# ProDoc_ChisFlash-Celebi.net
KiCad netlist of a schematic drawn in EasyEDA Pro
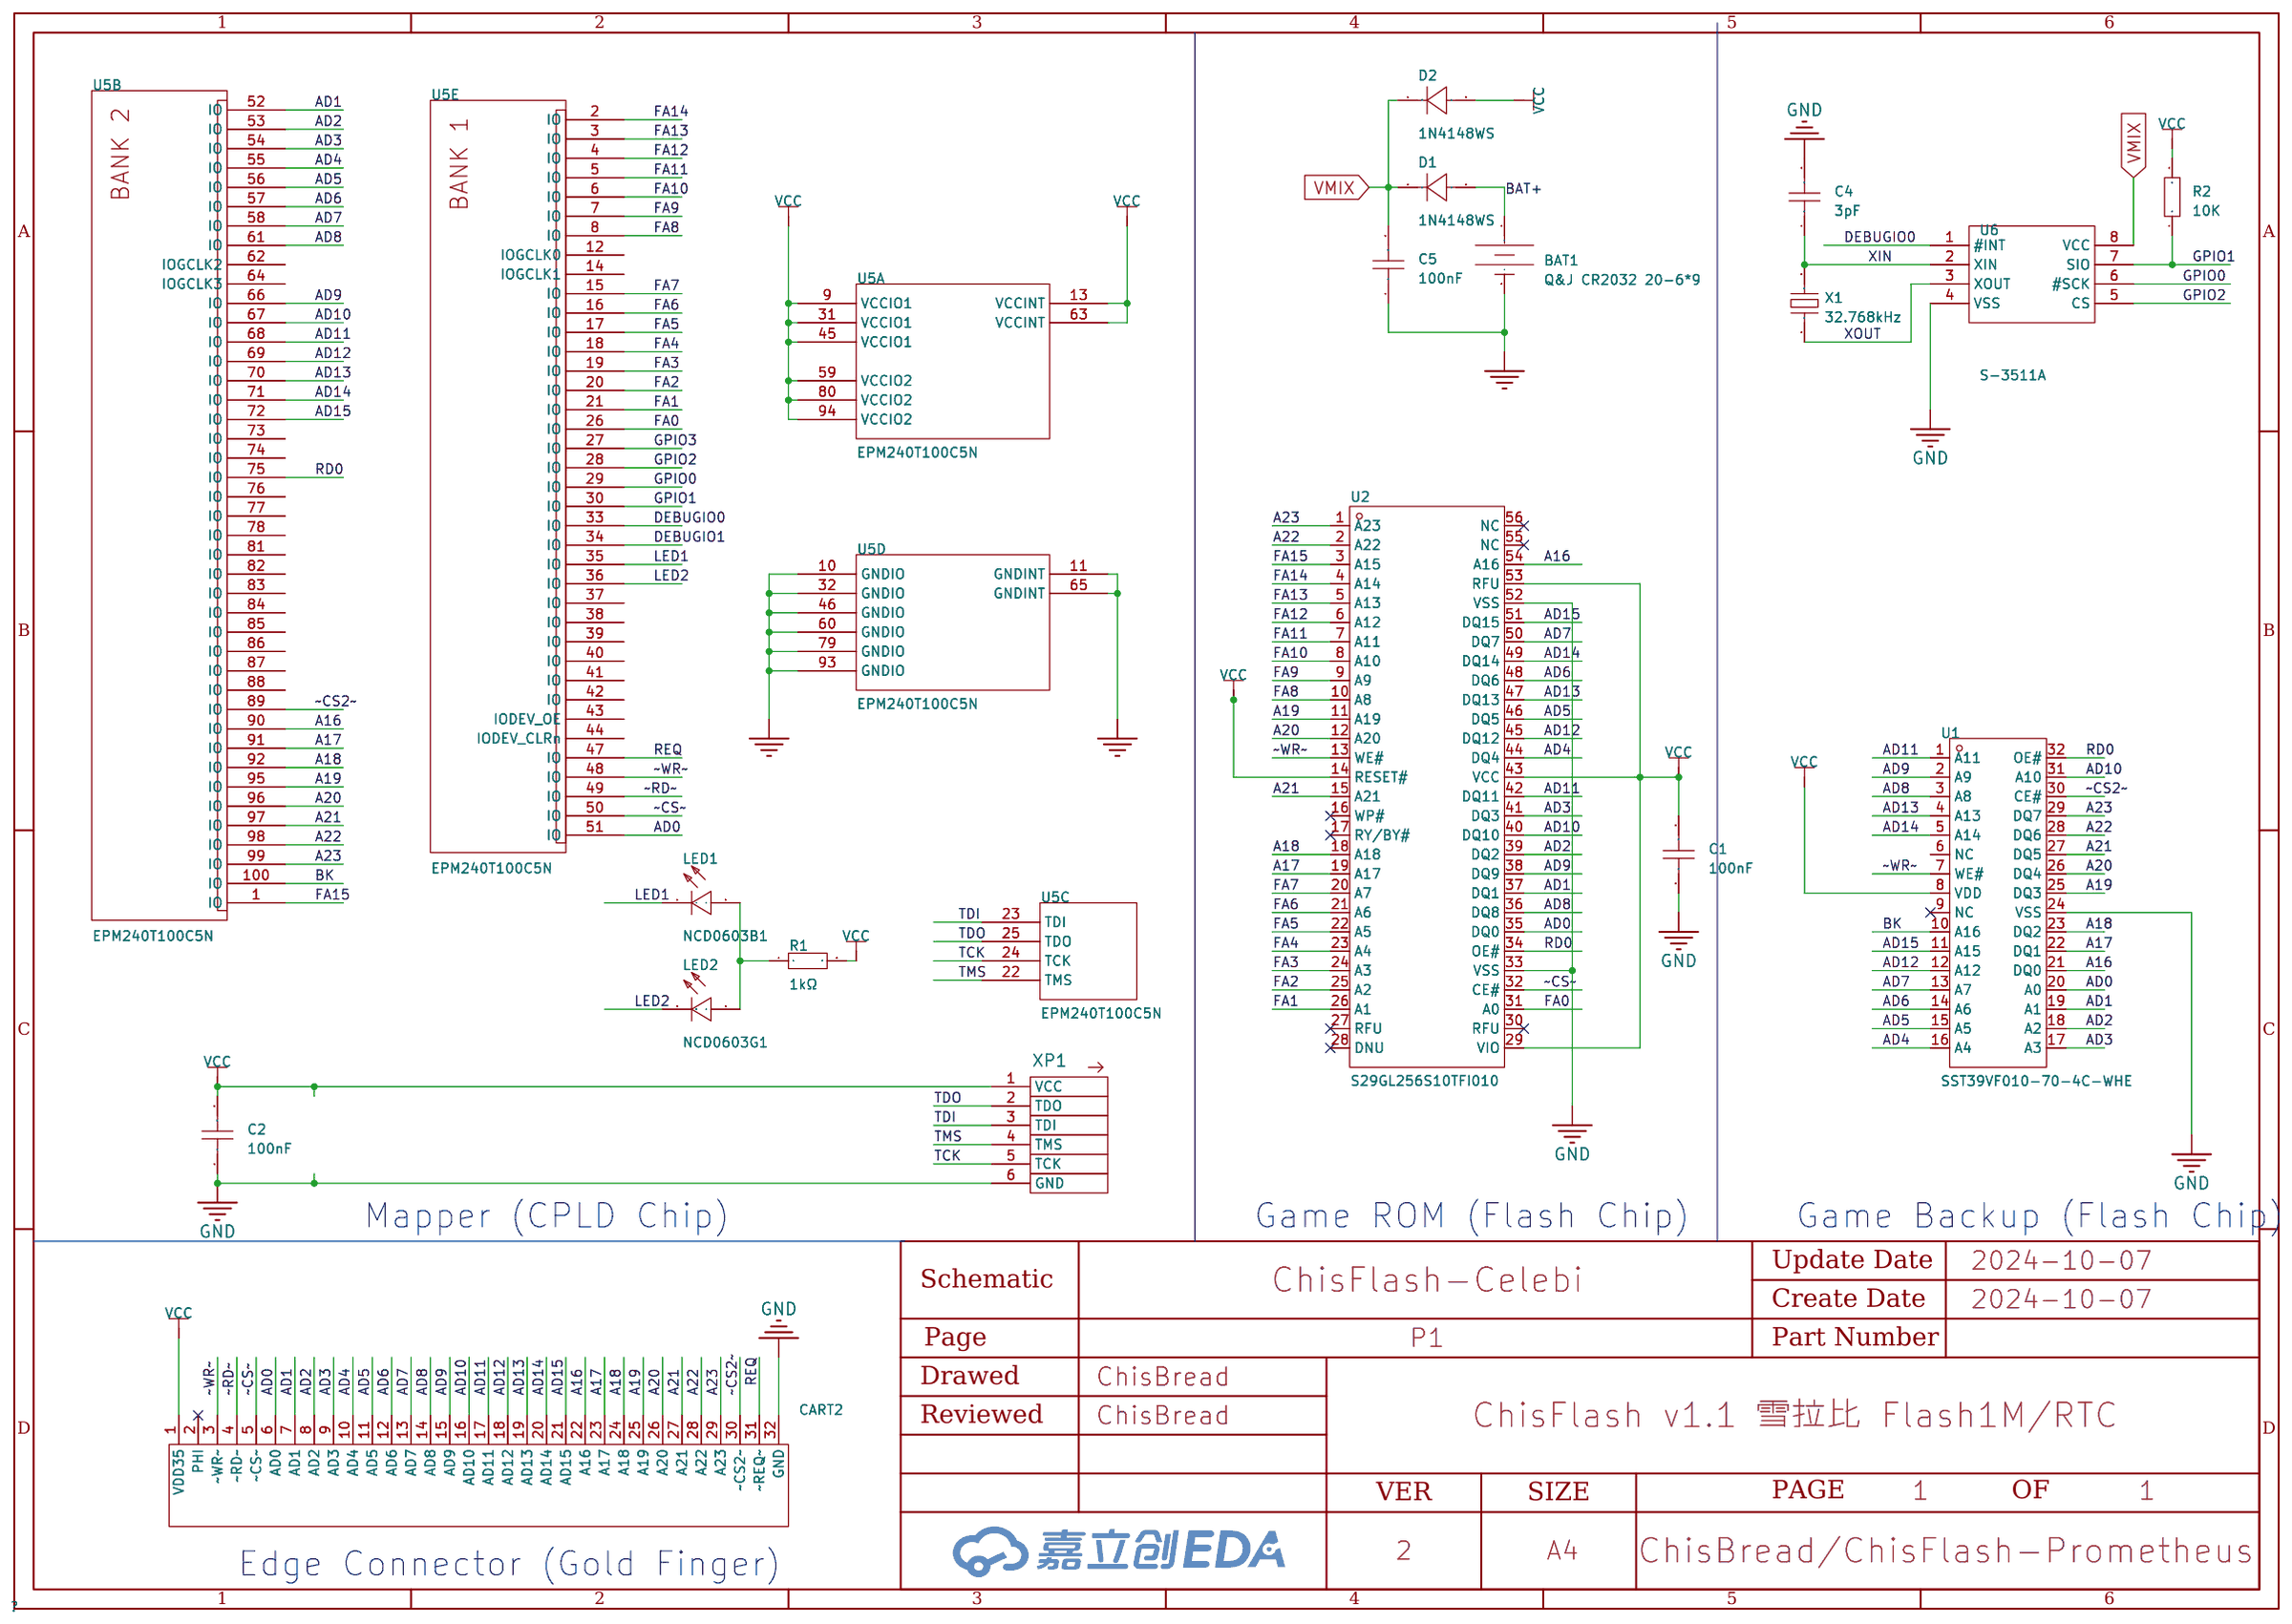
[diagram p0: schematic sheet]

(export (version "E")
  (design (tool "Eeschema 10.0.6"))
  (components
    (comp (ref "BAT1")
      (value "Q&J CR2032 20-6*9")
      (footprint "easyedapro:BAT-TH_CR2032")
      (description "直插")
      (fields (field (name "Manufacturer") "Q&J"))
      (libsource (lib "easyedapro") (part "BS-12-B3AA003-R"))
    )
    (comp (ref "C1")
      (value "100nF")
      (footprint "easyedapro:C0603")
      (libsource (lib "easyedapro") (part "CapAcitance"))
    )
    (comp (ref "C2")
      (value "100nF")
      (footprint "easyedapro:C0603")
      (libsource (lib "easyedapro") (part "CapAcitance"))
    )
    (comp (ref "C4")
      (value "3pF")
      (footprint "easyedapro:C0603")
      (libsource (lib "easyedapro") (part "CapAcitance"))
    )
    (comp (ref "C5")
      (value "100nF")
      (footprint "easyedapro:C0603")
      (libsource (lib "easyedapro") (part "CapAcitance"))
    )
    (comp (ref "CART2")
      (value "~")
      (footprint "easyedapro:GBA卡带金手指")
      (description "GBA卡带金手指")
      (libsource (lib "easyedapro") (part "GBA卡带金手指"))
    )
    (comp (ref "D1")
      (value "1N4148WS")
      (footprint "easyedapro:SOD-323_L1.8-W1.3-LS2.5-RD")
      (description "二极管配置:独立式;正向压降(Vf):1.25V@150mA;直流反向耐压(Vr):100V;平均整流电流(Io):300mA;功率:400mW;反向恢复时间(trr):8ns;")
      (fields (field (name "Manufacturer") "JSMSEMI(杰盛微)"))
      (libsource (lib "easyedapro") (part "1N4148WS_C917117"))
    )
    (comp (ref "D2")
      (value "1N4148WS")
      (footprint "easyedapro:SOD-323_L1.8-W1.3-LS2.5-RD")
      (description "二极管配置:独立式;正向压降(Vf):1.25V@150mA;直流反向耐压(Vr):100V;平均整流电流(Io):300mA;功率:400mW;反向恢复时间(trr):8ns;")
      (fields (field (name "Manufacturer") "JSMSEMI(杰盛微)"))
      (libsource (lib "easyedapro") (part "1N4148WS_C917117"))
    )
    (comp (ref "LED1")
      (value "NCD0603B1")
      (footprint "easyedapro:LED0603-RD")
      (fields (field (name "Manufacturer") "国星光电"))
      (libsource (lib "easyedapro") (part "FC-DA1608BK-470H10"))
    )
    (comp (ref "LED2")
      (value "NCD0603G1")
      (footprint "easyedapro:LED0603-RD")
      (fields (field (name "Manufacturer") "国星光电"))
      (libsource (lib "easyedapro") (part "FC-D1608UGK-520D10"))
    )
    (comp (ref "R1")
      (value "1kΩ")
      (footprint "easyedapro:R0603")
      (description "电阻类型:厚膜电阻;阻值:1kΩ;精度:±1%;功率:100mW;最大工作电压:75V;温度系数:±100ppm/°C;")
      (fields
        (field (name "Manufacturer Part") "0603WAF1001T5E")
        (field (name "Manufacturer") "UNI-ROYAL(厚声)")
      )
      (libsource (lib "easyedapro") (part "0603WAF1001T5E"))
    )
    (comp (ref "R2") (value "10K") (footprint "easyedapro:R0603") (libsource (lib "easyedapro") (part "电阻")))
    (comp (ref "U1")
      (value "SST39VF010-70-4C-WHE")
      (footprint "easyedapro:TSOP-32_L8.1-W12.5-P0.50-LS14.2-TL")
      (fields (field (name "Manufacturer") "MICROCHIP(美国微芯)"))
      (libsource (lib "easyedapro") (part "SST39VF010-70-4C-WHE"))
    )
    (comp (ref "U2")
      (value "S29GL256S10TFI010")
      (footprint "easyedapro:TSOP-56_L18.4-W14.0-P0.50-LS20.0-TL")
      (fields (field (name "Manufacturer") "SPANSION(飞索)"))
      (libsource (lib "easyedapro") (part "S29GL256S10TFI010"))
    )
    (comp (ref "U5")
      (value "EPM240T100C5N")
      (footprint "easyedapro:TQFP-100_L14.0-W14.0-P0.50-LS16.0-BL")
      (description "类型:其它PLD;逻辑门数量:-;逻辑单元数:-;逻辑阵列块数:240;")
      (fields (field (name "Manufacturer") "Intel/Altera"))
      (libsource (lib "easyedapro") (part "EPM240T100C5N"))
    )
    (comp (ref "U6")
      (value "S-3511A")
      (footprint "easyedapro:3511-sop8")
      (libsource (lib "easyedapro") (part "3511-SOP8"))
    )
    (comp (ref "X1")
      (value "32.768kHz")
      (footprint "easyedapro:OSC-SMD_L3.2-W1.5")
      (description "晶振类型:贴片晶振;频率:32.768kHz;常温频差:±20ppm;外接负载电容:12.5pF;频率稳定度(全温):-;")
      (fields (field (name "Manufacturer Part") "X321532768KGD2SI") (field (name "Manufacturer") "YXC(扬兴晶振)"))
      (libsource (lib "easyedapro") (part "X321532768KGD2SI"))
    )
    (comp (ref "XP1")
      (value "JTAG")
      (footprint "easyedapro:HDR-TH_6P-P1.27-V-M-1")
      (libsource (lib "easyedapro") (part "jtag"))
    )
  )
  (nets
    (net (code "1") (name "/A16") (class "Default")
      (node (ref "CART2") (pin "22") (pinfunction "A16_22") (pintype "input"))
      (node (ref "U1") (pin "21") (pinfunction "DQ0_21") (pintype "unspecified"))
      (node (ref "U2") (pin "54") (pinfunction "A16_54") (pintype "input"))
      (node (ref "U5") (pin "90") (pinfunction "IO_90") (pintype "bidirectional"))
    )
    (net (code "2") (name "/A17") (class "Default")
      (node (ref "CART2") (pin "23") (pinfunction "A17_23") (pintype "input"))
      (node (ref "U1") (pin "22") (pinfunction "DQ1_22") (pintype "unspecified"))
      (node (ref "U2") (pin "19") (pinfunction "A17_19") (pintype "input"))
      (node (ref "U5") (pin "91") (pinfunction "IO_91") (pintype "bidirectional"))
    )
    (net (code "3") (name "/A18") (class "Default")
      (node (ref "CART2") (pin "24") (pinfunction "A18_24") (pintype "input"))
      (node (ref "U1") (pin "23") (pinfunction "DQ2_23") (pintype "unspecified"))
      (node (ref "U2") (pin "18") (pinfunction "A18_18") (pintype "input"))
      (node (ref "U5") (pin "92") (pinfunction "IO_92") (pintype "bidirectional"))
    )
    (net (code "4") (name "/A19") (class "Default")
      (node (ref "CART2") (pin "25") (pinfunction "A19_25") (pintype "input"))
      (node (ref "U1") (pin "25") (pinfunction "DQ3_25") (pintype "unspecified"))
      (node (ref "U2") (pin "11") (pinfunction "A19_11") (pintype "input"))
      (node (ref "U5") (pin "95") (pinfunction "IO_95") (pintype "bidirectional"))
    )
    (net (code "5") (name "/A20") (class "Default")
      (node (ref "CART2") (pin "26") (pinfunction "A20_26") (pintype "input"))
      (node (ref "U1") (pin "26") (pinfunction "DQ4_26") (pintype "unspecified"))
      (node (ref "U2") (pin "12") (pinfunction "A20_12") (pintype "input"))
      (node (ref "U5") (pin "96") (pinfunction "IO_96") (pintype "bidirectional"))
    )
    (net (code "6") (name "/A21") (class "Default")
      (node (ref "CART2") (pin "27") (pinfunction "A21_27") (pintype "input"))
      (node (ref "U1") (pin "27") (pinfunction "DQ5_27") (pintype "unspecified"))
      (node (ref "U2") (pin "15") (pinfunction "A21_15") (pintype "input"))
      (node (ref "U5") (pin "97") (pinfunction "IO_97") (pintype "bidirectional"))
    )
    (net (code "7") (name "/A22") (class "Default")
      (node (ref "CART2") (pin "28") (pinfunction "A22_28") (pintype "input"))
      (node (ref "U1") (pin "28") (pinfunction "DQ6_28") (pintype "unspecified"))
      (node (ref "U2") (pin "2") (pinfunction "A22_2") (pintype "input"))
      (node (ref "U5") (pin "98") (pinfunction "IO_98") (pintype "bidirectional"))
    )
    (net (code "8") (name "/A23") (class "Default")
      (node (ref "CART2") (pin "29") (pinfunction "A23_29") (pintype "input"))
      (node (ref "U1") (pin "29") (pinfunction "DQ7_29") (pintype "unspecified"))
      (node (ref "U2") (pin "1") (pinfunction "A23_1") (pintype "input"))
      (node (ref "U5") (pin "99") (pinfunction "IO_99") (pintype "bidirectional"))
    )
    (net (code "9") (name "/AD0") (class "Default")
      (node (ref "CART2") (pin "6") (pinfunction "AD0_6") (pintype "input"))
      (node (ref "U1") (pin "20") (pinfunction "A0_20") (pintype "unspecified"))
      (node (ref "U2") (pin "35") (pinfunction "DQ0_35") (pintype "input"))
      (node (ref "U5") (pin "51") (pinfunction "IO_51") (pintype "bidirectional"))
    )
    (net (code "10") (name "/AD1") (class "Default")
      (node (ref "CART2") (pin "7") (pinfunction "AD1_7") (pintype "input"))
      (node (ref "U1") (pin "19") (pinfunction "A1_19") (pintype "unspecified"))
      (node (ref "U2") (pin "37") (pinfunction "DQ1_37") (pintype "input"))
      (node (ref "U5") (pin "52") (pinfunction "IO_52") (pintype "bidirectional"))
    )
    (net (code "11") (name "/AD2") (class "Default")
      (node (ref "CART2") (pin "8") (pinfunction "AD2_8") (pintype "input"))
      (node (ref "U1") (pin "18") (pinfunction "A2_18") (pintype "unspecified"))
      (node (ref "U2") (pin "39") (pinfunction "DQ2_39") (pintype "input"))
      (node (ref "U5") (pin "53") (pinfunction "IO_53") (pintype "bidirectional"))
    )
    (net (code "12") (name "/AD3") (class "Default")
      (node (ref "CART2") (pin "9") (pinfunction "AD3_9") (pintype "input"))
      (node (ref "U1") (pin "17") (pinfunction "A3_17") (pintype "unspecified"))
      (node (ref "U2") (pin "41") (pinfunction "DQ3_41") (pintype "input"))
      (node (ref "U5") (pin "54") (pinfunction "IO_54") (pintype "bidirectional"))
    )
    (net (code "13") (name "/AD4") (class "Default")
      (node (ref "CART2") (pin "10") (pinfunction "AD4_10") (pintype "input"))
      (node (ref "U1") (pin "16") (pinfunction "A4_16") (pintype "unspecified"))
      (node (ref "U2") (pin "44") (pinfunction "DQ4_44") (pintype "input"))
      (node (ref "U5") (pin "55") (pinfunction "IO_55") (pintype "bidirectional"))
    )
    (net (code "14") (name "/AD5") (class "Default")
      (node (ref "CART2") (pin "11") (pinfunction "AD5_11") (pintype "input"))
      (node (ref "U1") (pin "15") (pinfunction "A5_15") (pintype "unspecified"))
      (node (ref "U2") (pin "46") (pinfunction "DQ5_46") (pintype "input"))
      (node (ref "U5") (pin "56") (pinfunction "IO_56") (pintype "bidirectional"))
    )
    (net (code "15") (name "/AD6") (class "Default")
      (node (ref "CART2") (pin "12") (pinfunction "AD6_12") (pintype "input"))
      (node (ref "U1") (pin "14") (pinfunction "A6_14") (pintype "unspecified"))
      (node (ref "U2") (pin "48") (pinfunction "DQ6_48") (pintype "input"))
      (node (ref "U5") (pin "57") (pinfunction "IO_57") (pintype "bidirectional"))
    )
    (net (code "16") (name "/AD7") (class "Default")
      (node (ref "CART2") (pin "13") (pinfunction "AD7_13") (pintype "input"))
      (node (ref "U1") (pin "13") (pinfunction "A7_13") (pintype "unspecified"))
      (node (ref "U2") (pin "50") (pinfunction "DQ7_50") (pintype "input"))
      (node (ref "U5") (pin "58") (pinfunction "IO_58") (pintype "bidirectional"))
    )
    (net (code "17") (name "/AD8") (class "Default")
      (node (ref "CART2") (pin "14") (pinfunction "AD8_14") (pintype "input"))
      (node (ref "U1") (pin "3") (pinfunction "A8_3") (pintype "unspecified"))
      (node (ref "U2") (pin "36") (pinfunction "DQ8_36") (pintype "input"))
      (node (ref "U5") (pin "61") (pinfunction "IO_61") (pintype "bidirectional"))
    )
    (net (code "18") (name "/AD9") (class "Default")
      (node (ref "CART2") (pin "15") (pinfunction "AD9_15") (pintype "input"))
      (node (ref "U1") (pin "2") (pinfunction "A9_2") (pintype "unspecified"))
      (node (ref "U2") (pin "38") (pinfunction "DQ9_38") (pintype "input"))
      (node (ref "U5") (pin "66") (pinfunction "IO_66") (pintype "bidirectional"))
    )
    (net (code "19") (name "/AD10") (class "Default")
      (node (ref "CART2") (pin "16") (pinfunction "AD10_16") (pintype "input"))
      (node (ref "U1") (pin "31") (pinfunction "A10_31") (pintype "unspecified"))
      (node (ref "U2") (pin "40") (pinfunction "DQ10_40") (pintype "input"))
      (node (ref "U5") (pin "67") (pinfunction "IO_67") (pintype "bidirectional"))
    )
    (net (code "20") (name "/AD11") (class "Default")
      (node (ref "CART2") (pin "17") (pinfunction "AD11_17") (pintype "input"))
      (node (ref "U1") (pin "1") (pinfunction "A11_1") (pintype "unspecified"))
      (node (ref "U2") (pin "42") (pinfunction "DQ11_42") (pintype "input"))
      (node (ref "U5") (pin "68") (pinfunction "IO_68") (pintype "bidirectional"))
    )
    (net (code "21") (name "/AD12") (class "Default")
      (node (ref "CART2") (pin "18") (pinfunction "AD12_18") (pintype "input"))
      (node (ref "U1") (pin "12") (pinfunction "A12_12") (pintype "unspecified"))
      (node (ref "U2") (pin "45") (pinfunction "DQ12_45") (pintype "input"))
      (node (ref "U5") (pin "69") (pinfunction "IO_69") (pintype "bidirectional"))
    )
    (net (code "22") (name "/AD13") (class "Default")
      (node (ref "CART2") (pin "19") (pinfunction "AD13_19") (pintype "input"))
      (node (ref "U1") (pin "4") (pinfunction "A13_4") (pintype "unspecified"))
      (node (ref "U2") (pin "47") (pinfunction "DQ13_47") (pintype "input"))
      (node (ref "U5") (pin "70") (pinfunction "IO_70") (pintype "bidirectional"))
    )
    (net (code "23") (name "/AD14") (class "Default")
      (node (ref "CART2") (pin "20") (pinfunction "AD14_20") (pintype "input"))
      (node (ref "U1") (pin "5") (pinfunction "A14_5") (pintype "unspecified"))
      (node (ref "U2") (pin "49") (pinfunction "DQ14_49") (pintype "input"))
      (node (ref "U5") (pin "71") (pinfunction "IO_71") (pintype "bidirectional"))
    )
    (net (code "24") (name "/AD15") (class "Default")
      (node (ref "CART2") (pin "21") (pinfunction "AD15_21") (pintype "input"))
      (node (ref "U1") (pin "11") (pinfunction "A15_11") (pintype "unspecified"))
      (node (ref "U2") (pin "51") (pinfunction "DQ15_51") (pintype "input"))
      (node (ref "U5") (pin "72") (pinfunction "IO_72") (pintype "bidirectional"))
    )
    (net (code "25") (name "/BAT+") (class "Default")
      (node (ref "BAT1") (pin "1") (pinfunction "+_1") (pintype "unspecified"))
      (node (ref "D1") (pin "2") (pinfunction "A_2") (pintype "unspecified"))
    )
    (net (code "26") (name "/BK") (class "Default")
      (node (ref "U1") (pin "10") (pinfunction "A16_10") (pintype "unspecified"))
      (node (ref "U5") (pin "100") (pinfunction "IO_100") (pintype "bidirectional"))
    )
    (net (code "27") (name "/DEBUGIO0") (class "Default")
      (node (ref "U5") (pin "33") (pinfunction "IO_33") (pintype "bidirectional"))
      (node (ref "U6") (pin "1") (pinfunction "#INT_1") (pintype "input"))
    )
    (net (code "28") (name "/DEBUGIO1") (class "Default")
      (node (ref "U5") (pin "34") (pinfunction "IO_34") (pintype "bidirectional"))
    )
    (net (code "29") (name "/FA0") (class "Default")
      (node (ref "U2") (pin "31") (pinfunction "A0_31") (pintype "input"))
      (node (ref "U5") (pin "26") (pinfunction "IO_26") (pintype "bidirectional"))
    )
    (net (code "30") (name "/FA1") (class "Default")
      (node (ref "U2") (pin "26") (pinfunction "A1_26") (pintype "input"))
      (node (ref "U5") (pin "21") (pinfunction "IO_21") (pintype "bidirectional"))
    )
    (net (code "31") (name "/FA2") (class "Default")
      (node (ref "U2") (pin "25") (pinfunction "A2_25") (pintype "input"))
      (node (ref "U5") (pin "20") (pinfunction "IO_20") (pintype "bidirectional"))
    )
    (net (code "32") (name "/FA3") (class "Default")
      (node (ref "U2") (pin "24") (pinfunction "A3_24") (pintype "input"))
      (node (ref "U5") (pin "19") (pinfunction "IO_19") (pintype "bidirectional"))
    )
    (net (code "33") (name "/FA4") (class "Default")
      (node (ref "U2") (pin "23") (pinfunction "A4_23") (pintype "input"))
      (node (ref "U5") (pin "18") (pinfunction "IO_18") (pintype "bidirectional"))
    )
    (net (code "34") (name "/FA5") (class "Default")
      (node (ref "U2") (pin "22") (pinfunction "A5_22") (pintype "input"))
      (node (ref "U5") (pin "17") (pinfunction "IO_17") (pintype "bidirectional"))
    )
    (net (code "35") (name "/FA6") (class "Default")
      (node (ref "U2") (pin "21") (pinfunction "A6_21") (pintype "input"))
      (node (ref "U5") (pin "16") (pinfunction "IO_16") (pintype "bidirectional"))
    )
    (net (code "36") (name "/FA7") (class "Default")
      (node (ref "U2") (pin "20") (pinfunction "A7_20") (pintype "input"))
      (node (ref "U5") (pin "15") (pinfunction "IO_15") (pintype "bidirectional"))
    )
    (net (code "37") (name "/FA8") (class "Default")
      (node (ref "U2") (pin "10") (pinfunction "A8_10") (pintype "input"))
      (node (ref "U5") (pin "8") (pinfunction "IO_8") (pintype "bidirectional"))
    )
    (net (code "38") (name "/FA9") (class "Default")
      (node (ref "U2") (pin "9") (pinfunction "A9_9") (pintype "input"))
      (node (ref "U5") (pin "7") (pinfunction "IO_7") (pintype "bidirectional"))
    )
    (net (code "39") (name "/FA10") (class "Default")
      (node (ref "U2") (pin "8") (pinfunction "A10_8") (pintype "input"))
      (node (ref "U5") (pin "6") (pinfunction "IO_6") (pintype "bidirectional"))
    )
    (net (code "40") (name "/FA11") (class "Default")
      (node (ref "U2") (pin "7") (pinfunction "A11_7") (pintype "input"))
      (node (ref "U5") (pin "5") (pinfunction "IO_5") (pintype "bidirectional"))
    )
    (net (code "41") (name "/FA12") (class "Default")
      (node (ref "U2") (pin "6") (pinfunction "A12_6") (pintype "input"))
      (node (ref "U5") (pin "4") (pinfunction "IO_4") (pintype "bidirectional"))
    )
    (net (code "42") (name "/FA13") (class "Default")
      (node (ref "U2") (pin "5") (pinfunction "A13_5") (pintype "input"))
      (node (ref "U5") (pin "3") (pinfunction "IO_3") (pintype "bidirectional"))
    )
    (net (code "43") (name "/FA14") (class "Default")
      (node (ref "U2") (pin "4") (pinfunction "A14_4") (pintype "input"))
      (node (ref "U5") (pin "2") (pinfunction "IO_2") (pintype "bidirectional"))
    )
    (net (code "44") (name "/FA15") (class "Default")
      (node (ref "U2") (pin "3") (pinfunction "A15_3") (pintype "input"))
      (node (ref "U5") (pin "1") (pinfunction "IO_1") (pintype "bidirectional"))
    )
    (net (code "45") (name "/GPIO0") (class "Default")
      (node (ref "U5") (pin "29") (pinfunction "IO_29") (pintype "bidirectional"))
      (node (ref "U6") (pin "6") (pinfunction "#SCK_6") (pintype "input"))
    )
    (net (code "46") (name "/GPIO1") (class "Default")
      (node (ref "R2") (pin "1") (pinfunction "1_1") (pintype "input"))
      (node (ref "U5") (pin "30") (pinfunction "IO_30") (pintype "bidirectional"))
      (node (ref "U6") (pin "7") (pinfunction "SIO_7") (pintype "input"))
    )
    (net (code "47") (name "/GPIO2") (class "Default")
      (node (ref "U5") (pin "28") (pinfunction "IO_28") (pintype "bidirectional"))
      (node (ref "U6") (pin "5") (pinfunction "CS_5") (pintype "input"))
    )
    (net (code "48") (name "/GPIO3") (class "Default")
      (node (ref "U5") (pin "27") (pinfunction "IO_27") (pintype "bidirectional"))
    )
    (net (code "49") (name "/LED1") (class "Default")
      (node (ref "LED1") (pin "1") (pinfunction "-_1") (pintype "input"))
      (node (ref "U5") (pin "35") (pinfunction "IO_35") (pintype "bidirectional"))
    )
    (net (code "50") (name "/LED2") (class "Default")
      (node (ref "LED2") (pin "1") (pinfunction "K_1") (pintype "input"))
      (node (ref "U5") (pin "36") (pinfunction "IO_36") (pintype "bidirectional"))
    )
    (net (code "51") (name "/RD0") (class "Default")
      (node (ref "U1") (pin "32") (pinfunction "OE#_32") (pintype "unspecified"))
      (node (ref "U2") (pin "34") (pinfunction "OE#_34") (pintype "input"))
      (node (ref "U5") (pin "75") (pinfunction "IO_75") (pintype "bidirectional"))
    )
    (net (code "52") (name "/REQ") (class "Default")
      (node (ref "CART2") (pin "31") (pinfunction "~REQ~_31") (pintype "input"))
      (node (ref "U5") (pin "47") (pinfunction "IO_47") (pintype "bidirectional"))
    )
    (net (code "53") (name "/TCK") (class "Default")
      (node (ref "U5") (pin "24") (pinfunction "TCK_24") (pintype "unspecified"))
      (node (ref "XP1") (pin "5") (pinfunction "TCK_5") (pintype "input"))
    )
    (net (code "54") (name "/TDI") (class "Default")
      (node (ref "U5") (pin "23") (pinfunction "TDI_23") (pintype "unspecified"))
      (node (ref "XP1") (pin "3") (pinfunction "TDI_3") (pintype "output"))
    )
    (net (code "55") (name "/TDO") (class "Default")
      (node (ref "U5") (pin "25") (pinfunction "TDO_25") (pintype "output"))
      (node (ref "XP1") (pin "2") (pinfunction "TDO_2") (pintype "output"))
    )
    (net (code "56") (name "/TMS") (class "Default")
      (node (ref "U5") (pin "22") (pinfunction "TMS_22") (pintype "unspecified"))
      (node (ref "XP1") (pin "4") (pinfunction "TMS_4") (pintype "output"))
    )
    (net (code "57") (name "/XIN") (class "Default")
      (node (ref "C4") (pin "1") (pinfunction "1_1") (pintype "input"))
      (node (ref "U6") (pin "2") (pinfunction "XIN_2") (pintype "input"))
      (node (ref "X1") (pin "2") (pinfunction "2_2") (pintype "input"))
    )
    (net (code "58") (name "/XOUT") (class "Default")
      (node (ref "U6") (pin "3") (pinfunction "XOUT_3") (pintype "input"))
      (node (ref "X1") (pin "1") (pinfunction "1_1") (pintype "input"))
    )
    (net (code "59") (name "/~CS2~") (class "Default")
      (node (ref "CART2") (pin "30") (pinfunction "~CS2~_30") (pintype "input"))
      (node (ref "U1") (pin "30") (pinfunction "CE#_30") (pintype "unspecified"))
      (node (ref "U5") (pin "89") (pinfunction "IO_89") (pintype "bidirectional"))
    )
    (net (code "60") (name "/~CS~") (class "Default")
      (node (ref "CART2") (pin "5") (pinfunction "~CS~_5") (pintype "input"))
      (node (ref "U2") (pin "32") (pinfunction "CE#_32") (pintype "input"))
      (node (ref "U5") (pin "50") (pinfunction "IO_50") (pintype "bidirectional"))
    )
    (net (code "61") (name "/~RD~") (class "Default")
      (node (ref "CART2") (pin "4") (pinfunction "~RD~_4") (pintype "input"))
      (node (ref "U5") (pin "49") (pinfunction "IO_49") (pintype "bidirectional"))
    )
    (net (code "62") (name "/~WR~") (class "Default")
      (node (ref "CART2") (pin "3") (pinfunction "~WR~_3") (pintype "input"))
      (node (ref "U1") (pin "7") (pinfunction "WE#_7") (pintype "unspecified"))
      (node (ref "U2") (pin "13") (pinfunction "WE#_13") (pintype "input"))
      (node (ref "U5") (pin "48") (pinfunction "IO_48") (pintype "bidirectional"))
    )
    (net (code "63") (name "GND") (class "Default")
      (node (ref "BAT1") (pin "2") (pinfunction "-_2") (pintype "unspecified"))
      (node (ref "C1") (pin "1") (pinfunction "1_1") (pintype "input"))
      (node (ref "C2") (pin "1") (pinfunction "1_1") (pintype "input"))
      (node (ref "C4") (pin "2") (pinfunction "2_2") (pintype "input"))
      (node (ref "C5") (pin "1") (pinfunction "1_1") (pintype "input"))
      (node (ref "CART2") (pin "32") (pinfunction "GND_32") (pintype "input"))
      (node (ref "U1") (pin "24") (pinfunction "VSS_24") (pintype "unspecified"))
      (node (ref "U2") (pin "33") (pinfunction "VSS_33") (pintype "input"))
      (node (ref "U2") (pin "52") (pinfunction "VSS_52") (pintype "input"))
      (node (ref "U5") (pin "10") (pinfunction "GNDIO_10") (pintype "unspecified"))
      (node (ref "U5") (pin "11") (pinfunction "GNDINT_11") (pintype "unspecified"))
      (node (ref "U5") (pin "32") (pinfunction "GNDIO_32") (pintype "unspecified"))
      (node (ref "U5") (pin "46") (pinfunction "GNDIO_46") (pintype "unspecified"))
      (node (ref "U5") (pin "60") (pinfunction "GNDIO_60") (pintype "unspecified"))
      (node (ref "U5") (pin "65") (pinfunction "GNDINT_65") (pintype "unspecified"))
      (node (ref "U5") (pin "79") (pinfunction "GNDIO_79") (pintype "unspecified"))
      (node (ref "U5") (pin "93") (pinfunction "GNDIO_93") (pintype "unspecified"))
      (node (ref "U6") (pin "4") (pinfunction "VSS_4") (pintype "input"))
      (node (ref "XP1") (pin "6") (pinfunction "GND_6") (pintype "input"))
    )
    (net (code "64") (name "Net-(LED1-+)") (class "Default")
      (node (ref "LED1") (pin "2") (pinfunction "+_2") (pintype "input"))
      (node (ref "LED2") (pin "2") (pinfunction "A_2") (pintype "input"))
      (node (ref "R1") (pin "1") (pinfunction "1_1") (pintype "input"))
    )
    (net (code "65") (name "VCC") (class "Default")
      (node (ref "C1") (pin "2") (pinfunction "2_2") (pintype "input"))
      (node (ref "C2") (pin "2") (pinfunction "2_2") (pintype "input"))
      (node (ref "CART2") (pin "1") (pinfunction "VDD35_1") (pintype "input"))
      (node (ref "D2") (pin "2") (pinfunction "A_2") (pintype "unspecified"))
      (node (ref "R1") (pin "2") (pinfunction "2_2") (pintype "input"))
      (node (ref "R2") (pin "2") (pinfunction "2_2") (pintype "input"))
      (node (ref "U1") (pin "8") (pinfunction "VDD_8") (pintype "unspecified"))
      (node (ref "U2") (pin "14") (pinfunction "RESET#_14") (pintype "input"))
      (node (ref "U2") (pin "29") (pinfunction "VIO_29") (pintype "input"))
      (node (ref "U2") (pin "43") (pinfunction "VCC_43") (pintype "input"))
      (node (ref "U2") (pin "53") (pinfunction "RFU_53") (pintype "input"))
      (node (ref "U5") (pin "13") (pinfunction "VCCINT_13") (pintype "unspecified"))
      (node (ref "U5") (pin "31") (pinfunction "VCCIO1_31") (pintype "unspecified"))
      (node (ref "U5") (pin "45") (pinfunction "VCCIO1_45") (pintype "unspecified"))
      (node (ref "U5") (pin "59") (pinfunction "VCCIO2_59") (pintype "unspecified"))
      (node (ref "U5") (pin "63") (pinfunction "VCCINT_63") (pintype "unspecified"))
      (node (ref "U5") (pin "80") (pinfunction "VCCIO2_80") (pintype "unspecified"))
      (node (ref "U5") (pin "9") (pinfunction "VCCIO1_9") (pintype "unspecified"))
      (node (ref "U5") (pin "94") (pinfunction "VCCIO2_94") (pintype "unspecified"))
      (node (ref "XP1") (pin "1") (pinfunction "VCC_1") (pintype "output"))
    )
    (net (code "66") (name "VMIX") (class "Default")
      (node (ref "C5") (pin "2") (pinfunction "2_2") (pintype "input"))
      (node (ref "D1") (pin "1") (pinfunction "C_1") (pintype "unspecified"))
      (node (ref "D2") (pin "1") (pinfunction "C_1") (pintype "unspecified"))
      (node (ref "U6") (pin "8") (pinfunction "VCC_8") (pintype "input"))
    )
    (net (code "67") (name "unconnected-(CART2-PHI-Pad2)") (class "Default")
      (node (ref "CART2") (pin "2") (pinfunction "PHI_2") (pintype "input+no_connect"))
    )
    (net (code "68") (name "unconnected-(U1-NC-Pad6)") (class "Default")
      (node (ref "U1") (pin "6") (pinfunction "NC_6") (pintype "unspecified"))
    )
    (net (code "69") (name "unconnected-(U1-NC-Pad9)") (class "Default")
      (node (ref "U1") (pin "9") (pinfunction "NC_9") (pintype "unspecified+no_connect"))
    )
    (net (code "70") (name "unconnected-(U2-DNU-Pad28)") (class "Default")
      (node (ref "U2") (pin "28") (pinfunction "DNU_28") (pintype "input+no_connect"))
    )
    (net (code "71") (name "unconnected-(U2-NC-Pad55)") (class "Default")
      (node (ref "U2") (pin "55") (pinfunction "NC_55") (pintype "input+no_connect"))
    )
    (net (code "72") (name "unconnected-(U2-NC-Pad56)") (class "Default")
      (node (ref "U2") (pin "56") (pinfunction "NC_56") (pintype "input+no_connect"))
    )
    (net (code "73") (name "unconnected-(U2-RFU-Pad27)") (class "Default")
      (node (ref "U2") (pin "27") (pinfunction "RFU_27") (pintype "input+no_connect"))
    )
    (net (code "74") (name "unconnected-(U2-RFU-Pad30)") (class "Default")
      (node (ref "U2") (pin "30") (pinfunction "RFU_30") (pintype "input+no_connect"))
    )
    (net (code "75") (name "unconnected-(U2-RY{slash}BY#-Pad17)") (class "Default")
      (node (ref "U2") (pin "17") (pinfunction "RY/BY#_17") (pintype "input+no_connect"))
    )
    (net (code "76") (name "unconnected-(U2-WP#-Pad16)") (class "Default")
      (node (ref "U2") (pin "16") (pinfunction "WP#_16") (pintype "input+no_connect"))
    )
    (net (code "77") (name "unconnected-(U5B-IO-Pad73)") (class "Default")
      (node (ref "U5") (pin "73") (pinfunction "IO_73") (pintype "bidirectional"))
    )
    (net (code "78") (name "unconnected-(U5B-IO-Pad74)") (class "Default")
      (node (ref "U5") (pin "74") (pinfunction "IO_74") (pintype "bidirectional"))
    )
    (net (code "79") (name "unconnected-(U5B-IO-Pad76)") (class "Default")
      (node (ref "U5") (pin "76") (pinfunction "IO_76") (pintype "bidirectional"))
    )
    (net (code "80") (name "unconnected-(U5B-IO-Pad77)") (class "Default")
      (node (ref "U5") (pin "77") (pinfunction "IO_77") (pintype "bidirectional"))
    )
    (net (code "81") (name "unconnected-(U5B-IO-Pad78)") (class "Default")
      (node (ref "U5") (pin "78") (pinfunction "IO_78") (pintype "bidirectional"))
    )
    (net (code "82") (name "unconnected-(U5B-IO-Pad81)") (class "Default")
      (node (ref "U5") (pin "81") (pinfunction "IO_81") (pintype "bidirectional"))
    )
    (net (code "83") (name "unconnected-(U5B-IO-Pad82)") (class "Default")
      (node (ref "U5") (pin "82") (pinfunction "IO_82") (pintype "bidirectional"))
    )
    (net (code "84") (name "unconnected-(U5B-IO-Pad83)") (class "Default")
      (node (ref "U5") (pin "83") (pinfunction "IO_83") (pintype "bidirectional"))
    )
    (net (code "85") (name "unconnected-(U5B-IO-Pad84)") (class "Default")
      (node (ref "U5") (pin "84") (pinfunction "IO_84") (pintype "bidirectional"))
    )
    (net (code "86") (name "unconnected-(U5B-IO-Pad85)") (class "Default")
      (node (ref "U5") (pin "85") (pinfunction "IO_85") (pintype "bidirectional"))
    )
    (net (code "87") (name "unconnected-(U5B-IO-Pad86)") (class "Default")
      (node (ref "U5") (pin "86") (pinfunction "IO_86") (pintype "bidirectional"))
    )
    (net (code "88") (name "unconnected-(U5B-IO-Pad87)") (class "Default")
      (node (ref "U5") (pin "87") (pinfunction "IO_87") (pintype "bidirectional"))
    )
    (net (code "89") (name "unconnected-(U5B-IO-Pad88)") (class "Default")
      (node (ref "U5") (pin "88") (pinfunction "IO_88") (pintype "bidirectional"))
    )
    (net (code "90") (name "unconnected-(U5B-IOGCLK2-Pad62)") (class "Default")
      (node (ref "U5") (pin "62") (pinfunction "IOGCLK2_62") (pintype "bidirectional"))
    )
    (net (code "91") (name "unconnected-(U5B-IOGCLK3-Pad64)") (class "Default")
      (node (ref "U5") (pin "64") (pinfunction "IOGCLK3_64") (pintype "bidirectional"))
    )
    (net (code "92") (name "unconnected-(U5E-IO-Pad37)") (class "Default")
      (node (ref "U5") (pin "37") (pinfunction "IO_37") (pintype "bidirectional"))
    )
    (net (code "93") (name "unconnected-(U5E-IO-Pad38)") (class "Default")
      (node (ref "U5") (pin "38") (pinfunction "IO_38") (pintype "bidirectional"))
    )
    (net (code "94") (name "unconnected-(U5E-IO-Pad39)") (class "Default")
      (node (ref "U5") (pin "39") (pinfunction "IO_39") (pintype "bidirectional"))
    )
    (net (code "95") (name "unconnected-(U5E-IO-Pad40)") (class "Default")
      (node (ref "U5") (pin "40") (pinfunction "IO_40") (pintype "bidirectional"))
    )
    (net (code "96") (name "unconnected-(U5E-IO-Pad41)") (class "Default")
      (node (ref "U5") (pin "41") (pinfunction "IO_41") (pintype "bidirectional"))
    )
    (net (code "97") (name "unconnected-(U5E-IO-Pad42)") (class "Default")
      (node (ref "U5") (pin "42") (pinfunction "IO_42") (pintype "bidirectional"))
    )
    (net (code "98") (name "unconnected-(U5E-IODEV_CLRn-Pad44)") (class "Default")
      (node (ref "U5") (pin "44") (pinfunction "IODEV_CLRn_44") (pintype "bidirectional"))
    )
    (net (code "99") (name "unconnected-(U5E-IODEV_OE-Pad43)") (class "Default")
      (node (ref "U5") (pin "43") (pinfunction "IODEV_OE_43") (pintype "bidirectional"))
    )
    (net (code "100") (name "unconnected-(U5E-IOGCLK0-Pad12)") (class "Default")
      (node (ref "U5") (pin "12") (pinfunction "IOGCLK0_12") (pintype "bidirectional"))
    )
    (net (code "101") (name "unconnected-(U5E-IOGCLK1-Pad14)") (class "Default")
      (node (ref "U5") (pin "14") (pinfunction "IOGCLK1_14") (pintype "bidirectional"))
    )
  )
)
